# I2C_Line_Sensor.net
KiCad netlist of a schematic drawn in EAGLE
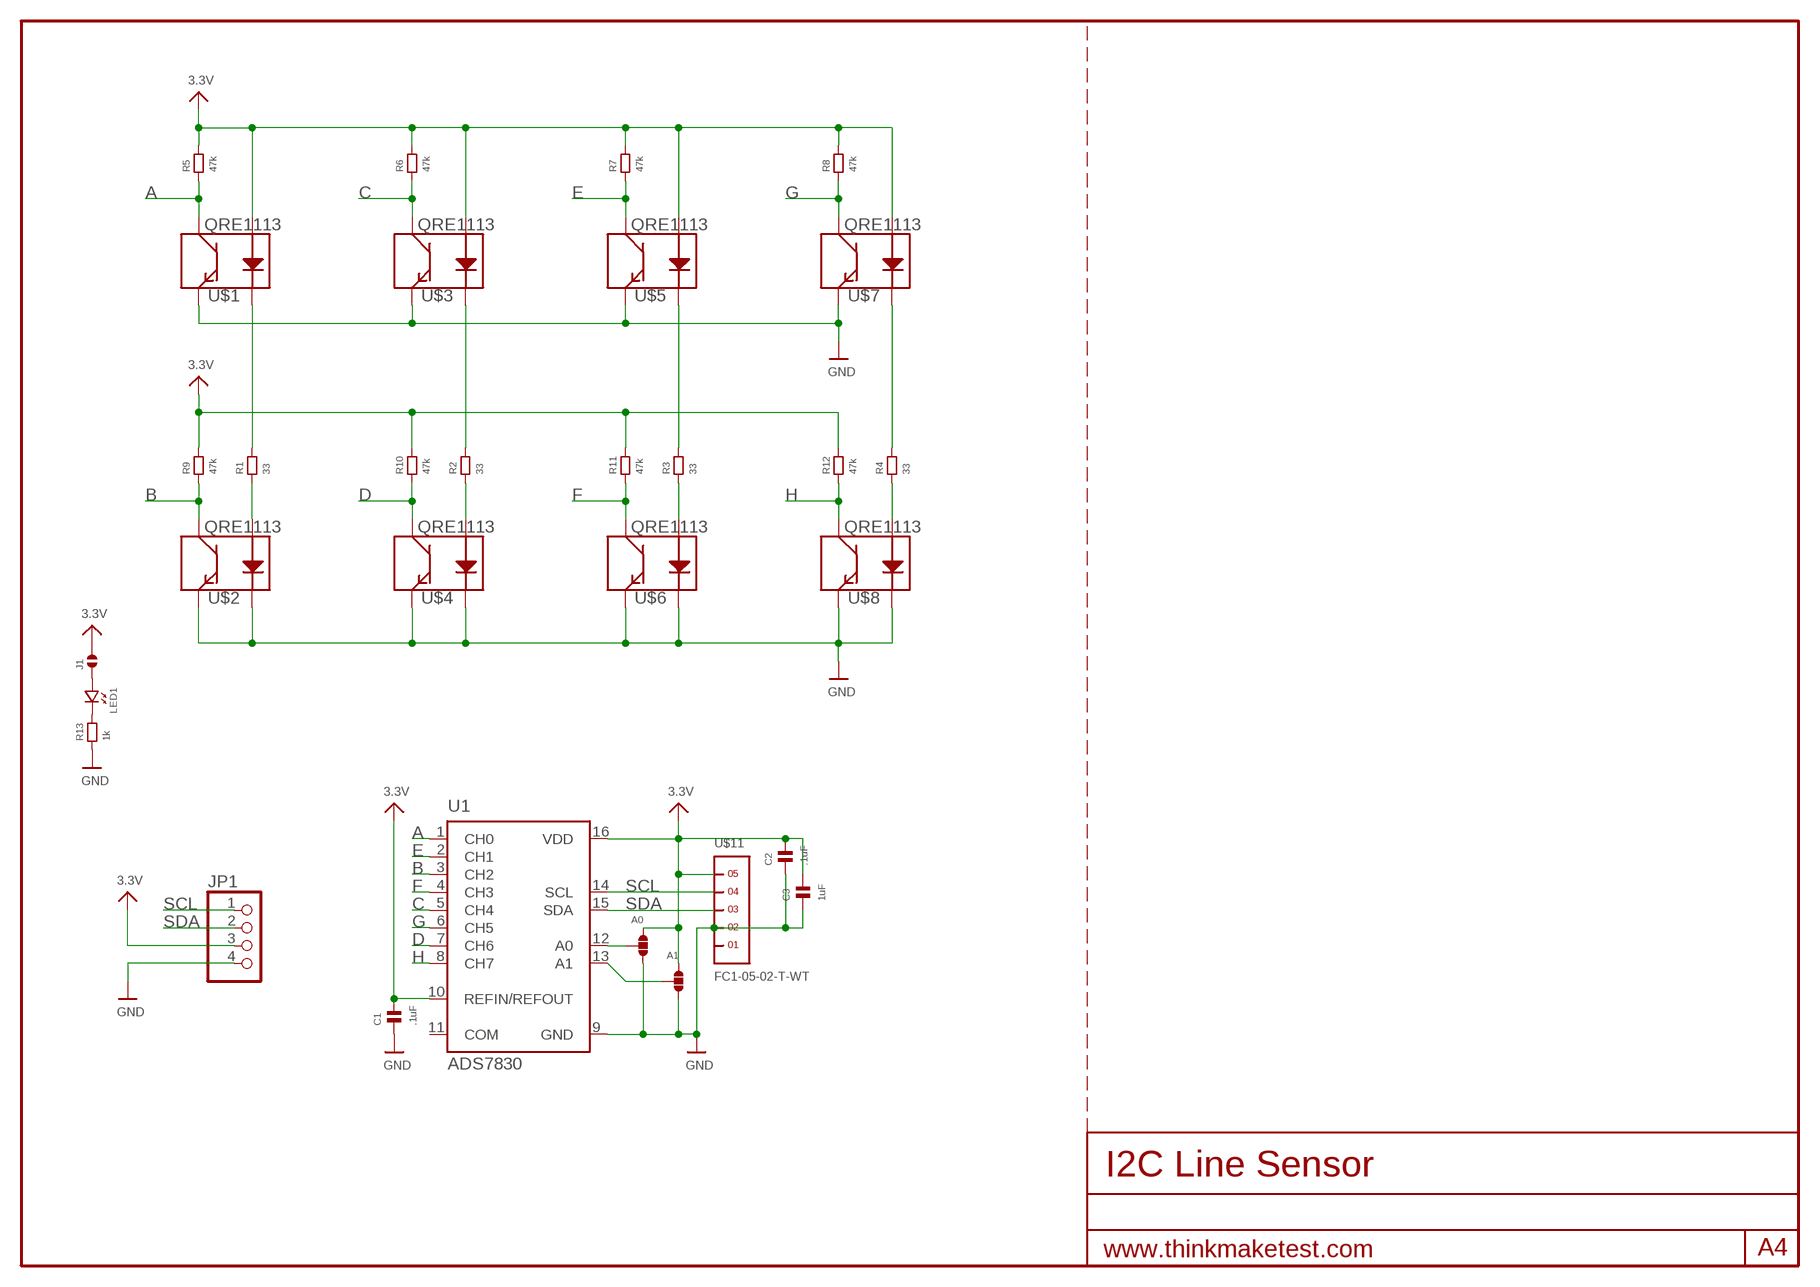
[diagram p0: schematic, sheet 1]

(export (version "E")
  (design (tool "Eeschema 10.0.6"))
  (components
    (comp (ref "A0")
      (value "SOLDERJUMPER.3.LRG.23")
      (footprint "eagle-import:3.LRG.23")
      (libsource (lib "eagle-import") (part "SOLDERJUMPER.3.LRG.23"))
    )
    (comp (ref "A1")
      (value "SOLDERJUMPER.3.LRG.23")
      (footprint "eagle-import:3.LRG.23")
      (libsource (lib "eagle-import") (part "SOLDERJUMPER.3.LRG.23"))
    )
    (comp (ref "C1")
      (value ".1uF")
      (footprint "eagle-import:0603")
      (libsource (lib "eagle-import") (part "CAPACITOR.0603"))
    )
    (comp (ref "C2")
      (value ".1uF")
      (footprint "eagle-import:0603")
      (libsource (lib "eagle-import") (part "CAPACITOR.0603"))
    )
    (comp (ref "C3")
      (value "1uF")
      (footprint "eagle-import:0603")
      (libsource (lib "eagle-import") (part "CAPACITOR.0603"))
    )
    (comp (ref "J1")
      (value "SOLDERJUMPER.2.MED")
      (footprint "eagle-import:2.MED")
      (libsource (lib "eagle-import") (part "SOLDERJUMPER.2.MED"))
    )
    (comp (ref "JP1")
      (value "HEADER-1X4")
      (footprint "eagle-import:1X04_OVAL")
      (libsource (lib "eagle-import") (part "HEADER-1X4"))
    )
    (comp (ref "LED1")
      (value "LED.0603")
      (footprint "eagle-import:0603.LED")
      (libsource (lib "eagle-import") (part "LED.0603"))
    )
    (comp (ref "R1")
      (value "33")
      (footprint "eagle-import:0603")
      (libsource (lib "eagle-import") (part "RESISTOR.0603"))
    )
    (comp (ref "R2")
      (value "33")
      (footprint "eagle-import:0603")
      (libsource (lib "eagle-import") (part "RESISTOR.0603"))
    )
    (comp (ref "R3")
      (value "33")
      (footprint "eagle-import:0603")
      (libsource (lib "eagle-import") (part "RESISTOR.0603"))
    )
    (comp (ref "R4")
      (value "33")
      (footprint "eagle-import:0603")
      (libsource (lib "eagle-import") (part "RESISTOR.0603"))
    )
    (comp (ref "R5")
      (value "47k")
      (footprint "eagle-import:0603")
      (libsource (lib "eagle-import") (part "RESISTOR.0603"))
    )
    (comp (ref "R6")
      (value "47k")
      (footprint "eagle-import:0603")
      (libsource (lib "eagle-import") (part "RESISTOR.0603"))
    )
    (comp (ref "R7")
      (value "47k")
      (footprint "eagle-import:0603")
      (libsource (lib "eagle-import") (part "RESISTOR.0603"))
    )
    (comp (ref "R8")
      (value "47k")
      (footprint "eagle-import:0603")
      (libsource (lib "eagle-import") (part "RESISTOR.0603"))
    )
    (comp (ref "R9")
      (value "47k")
      (footprint "eagle-import:0603")
      (libsource (lib "eagle-import") (part "RESISTOR.0603"))
    )
    (comp (ref "R10")
      (value "47k")
      (footprint "eagle-import:0603")
      (libsource (lib "eagle-import") (part "RESISTOR.0603"))
    )
    (comp (ref "R11")
      (value "47k")
      (footprint "eagle-import:0603")
      (libsource (lib "eagle-import") (part "RESISTOR.0603"))
    )
    (comp (ref "R12")
      (value "47k")
      (footprint "eagle-import:0603")
      (libsource (lib "eagle-import") (part "RESISTOR.0603"))
    )
    (comp (ref "R13")
      (value "1k")
      (footprint "eagle-import:0603")
      (libsource (lib "eagle-import") (part "RESISTOR.0603"))
    )
    (comp (ref "U$1")
      (value "QRE1113")
      (footprint "eagle-import:QRE1113")
      (libsource (lib "eagle-import") (part "QRE1113"))
    )
    (comp (ref "U$2")
      (value "QRE1113")
      (footprint "eagle-import:QRE1113")
      (libsource (lib "eagle-import") (part "QRE1113"))
    )
    (comp (ref "U$3")
      (value "QRE1113")
      (footprint "eagle-import:QRE1113")
      (libsource (lib "eagle-import") (part "QRE1113"))
    )
    (comp (ref "U$4")
      (value "QRE1113")
      (footprint "eagle-import:QRE1113")
      (libsource (lib "eagle-import") (part "QRE1113"))
    )
    (comp (ref "U$5")
      (value "QRE1113")
      (footprint "eagle-import:QRE1113")
      (libsource (lib "eagle-import") (part "QRE1113"))
    )
    (comp (ref "U$6")
      (value "QRE1113")
      (footprint "eagle-import:QRE1113")
      (libsource (lib "eagle-import") (part "QRE1113"))
    )
    (comp (ref "U$7")
      (value "QRE1113")
      (footprint "eagle-import:QRE1113")
      (libsource (lib "eagle-import") (part "QRE1113"))
    )
    (comp (ref "U$8")
      (value "QRE1113")
      (footprint "eagle-import:QRE1113")
      (libsource (lib "eagle-import") (part "QRE1113"))
    )
    (comp (ref "U$11")
      (value "FC1-05-02-T-WT")
      (footprint "eagle-import:FC1-05-02-T-WT")
      (libsource (lib "eagle-import") (part "FC1-05-02-T-WT"))
    )
    (comp (ref "U1")
      (value "ADS7830")
      (footprint "eagle-import:TSSOP16-PW")
      (libsource (lib "eagle-import") (part "ADS7828"))
    )
  )
  (nets
    (net (code "1") (name "/A") (class "Default")
      (node (ref "R5") (pin "1") (pinfunction "1_1") (pintype "bidirectional"))
      (node (ref "U$1") (pin "3") (pinfunction "C_3") (pintype "bidirectional"))
      (node (ref "U1") (pin "1") (pinfunction "CH0_1") (pintype "input"))
    )
    (net (code "2") (name "/B") (class "Default")
      (node (ref "R9") (pin "1") (pinfunction "1_1") (pintype "bidirectional"))
      (node (ref "U$2") (pin "3") (pinfunction "C_3") (pintype "bidirectional"))
      (node (ref "U1") (pin "3") (pinfunction "CH2_3") (pintype "input"))
    )
    (net (code "3") (name "/C") (class "Default")
      (node (ref "R6") (pin "1") (pinfunction "1_1") (pintype "bidirectional"))
      (node (ref "U$3") (pin "3") (pinfunction "C_3") (pintype "bidirectional"))
      (node (ref "U1") (pin "5") (pinfunction "CH4_5") (pintype "input"))
    )
    (net (code "4") (name "/D") (class "Default")
      (node (ref "R10") (pin "1") (pinfunction "1_1") (pintype "bidirectional"))
      (node (ref "U$4") (pin "3") (pinfunction "C_3") (pintype "bidirectional"))
      (node (ref "U1") (pin "7") (pinfunction "CH6_7") (pintype "input"))
    )
    (net (code "5") (name "/E") (class "Default")
      (node (ref "R7") (pin "1") (pinfunction "1_1") (pintype "bidirectional"))
      (node (ref "U$5") (pin "3") (pinfunction "C_3") (pintype "bidirectional"))
      (node (ref "U1") (pin "2") (pinfunction "CH1_2") (pintype "input"))
    )
    (net (code "6") (name "/F") (class "Default")
      (node (ref "R11") (pin "1") (pinfunction "1_1") (pintype "bidirectional"))
      (node (ref "U$6") (pin "3") (pinfunction "C_3") (pintype "bidirectional"))
      (node (ref "U1") (pin "4") (pinfunction "CH3_4") (pintype "input"))
    )
    (net (code "7") (name "/G") (class "Default")
      (node (ref "R8") (pin "1") (pinfunction "1_1") (pintype "bidirectional"))
      (node (ref "U$7") (pin "3") (pinfunction "C_3") (pintype "bidirectional"))
      (node (ref "U1") (pin "6") (pinfunction "CH5_6") (pintype "input"))
    )
    (net (code "8") (name "/H") (class "Default")
      (node (ref "R12") (pin "1") (pinfunction "1_1") (pintype "bidirectional"))
      (node (ref "U$8") (pin "3") (pinfunction "C_3") (pintype "bidirectional"))
      (node (ref "U1") (pin "8") (pinfunction "CH7_8") (pintype "input"))
    )
    (net (code "9") (name "/SCL") (class "Default")
      (node (ref "JP1") (pin "1") (pinfunction "1_1") (pintype "passive"))
      (node (ref "U$11") (pin "4") (pinfunction "4_4") (pintype "bidirectional"))
      (node (ref "U1") (pin "14") (pinfunction "SCL_14") (pintype "input"))
    )
    (net (code "10") (name "/SDA") (class "Default")
      (node (ref "JP1") (pin "2") (pinfunction "2_2") (pintype "passive"))
      (node (ref "U$11") (pin "3") (pinfunction "3_3") (pintype "bidirectional"))
      (node (ref "U1") (pin "15") (pinfunction "SDA_15") (pintype "bidirectional"))
    )
    (net (code "11") (name "3.3V") (class "Default")
      (node (ref "A0") (pin "1") (pinfunction "1_1") (pintype "bidirectional"))
      (node (ref "A1") (pin "1") (pinfunction "1_1") (pintype "bidirectional"))
      (node (ref "C1") (pin "2") (pinfunction "2_2") (pintype "bidirectional"))
      (node (ref "C2") (pin "2") (pinfunction "2_2") (pintype "bidirectional"))
      (node (ref "C3") (pin "2") (pinfunction "2_2") (pintype "bidirectional"))
      (node (ref "J1") (pin "2") (pinfunction "2_2") (pintype "bidirectional"))
      (node (ref "JP1") (pin "3") (pinfunction "3_3") (pintype "passive"))
      (node (ref "R10") (pin "2") (pinfunction "2_2") (pintype "bidirectional"))
      (node (ref "R11") (pin "2") (pinfunction "2_2") (pintype "bidirectional"))
      (node (ref "R12") (pin "2") (pinfunction "2_2") (pintype "bidirectional"))
      (node (ref "R5") (pin "2") (pinfunction "2_2") (pintype "bidirectional"))
      (node (ref "R6") (pin "2") (pinfunction "2_2") (pintype "bidirectional"))
      (node (ref "R7") (pin "2") (pinfunction "2_2") (pintype "bidirectional"))
      (node (ref "R8") (pin "2") (pinfunction "2_2") (pintype "bidirectional"))
      (node (ref "R9") (pin "2") (pinfunction "2_2") (pintype "bidirectional"))
      (node (ref "U$1") (pin "1") (pinfunction "A_1") (pintype "bidirectional"))
      (node (ref "U$11") (pin "5") (pinfunction "5_5") (pintype "bidirectional"))
      (node (ref "U$3") (pin "1") (pinfunction "A_1") (pintype "bidirectional"))
      (node (ref "U$5") (pin "1") (pinfunction "A_1") (pintype "bidirectional"))
      (node (ref "U$7") (pin "1") (pinfunction "A_1") (pintype "bidirectional"))
      (node (ref "U1") (pin "10") (pinfunction "REFIN/REFOUT_10") (pintype "passive"))
      (node (ref "U1") (pin "16") (pinfunction "VDD_16") (pintype "power_in"))
    )
    (net (code "12") (name "GND") (class "Default")
      (node (ref "A0") (pin "3") (pinfunction "3_3") (pintype "bidirectional"))
      (node (ref "A1") (pin "3") (pinfunction "3_3") (pintype "bidirectional"))
      (node (ref "C1") (pin "1") (pinfunction "1_1") (pintype "bidirectional"))
      (node (ref "C2") (pin "1") (pinfunction "1_1") (pintype "bidirectional"))
      (node (ref "C3") (pin "1") (pinfunction "1_1") (pintype "bidirectional"))
      (node (ref "JP1") (pin "4") (pinfunction "4_4") (pintype "passive"))
      (node (ref "R13") (pin "1") (pinfunction "1_1") (pintype "bidirectional"))
      (node (ref "U$1") (pin "4") (pinfunction "E_4") (pintype "bidirectional"))
      (node (ref "U$11") (pin "2") (pinfunction "2_2") (pintype "bidirectional"))
      (node (ref "U$2") (pin "2") (pinfunction "K_2") (pintype "bidirectional"))
      (node (ref "U$2") (pin "4") (pinfunction "E_4") (pintype "bidirectional"))
      (node (ref "U$3") (pin "4") (pinfunction "E_4") (pintype "bidirectional"))
      (node (ref "U$4") (pin "2") (pinfunction "K_2") (pintype "bidirectional"))
      (node (ref "U$4") (pin "4") (pinfunction "E_4") (pintype "bidirectional"))
      (node (ref "U$5") (pin "4") (pinfunction "E_4") (pintype "bidirectional"))
      (node (ref "U$6") (pin "2") (pinfunction "K_2") (pintype "bidirectional"))
      (node (ref "U$6") (pin "4") (pinfunction "E_4") (pintype "bidirectional"))
      (node (ref "U$7") (pin "4") (pinfunction "E_4") (pintype "bidirectional"))
      (node (ref "U$8") (pin "2") (pinfunction "K_2") (pintype "bidirectional"))
      (node (ref "U$8") (pin "4") (pinfunction "E_4") (pintype "bidirectional"))
      (node (ref "U1") (pin "9") (pinfunction "GND_9") (pintype "power_in"))
    )
    (net (code "13") (name "Net-(LED1-1)") (class "Default")
      (node (ref "J1") (pin "1") (pinfunction "1_1") (pintype "bidirectional"))
      (node (ref "LED1") (pin "P$1") (pinfunction "1_P$1") (pintype "bidirectional"))
    )
    (net (code "14") (name "Net-(LED1-2)") (class "Default")
      (node (ref "LED1") (pin "P$2") (pinfunction "2_P$2") (pintype "bidirectional"))
      (node (ref "R13") (pin "2") (pinfunction "2_2") (pintype "bidirectional"))
    )
    (net (code "15") (name "Net-(U$1-K)") (class "Default")
      (node (ref "R1") (pin "2") (pinfunction "2_2") (pintype "bidirectional"))
      (node (ref "U$1") (pin "2") (pinfunction "K_2") (pintype "bidirectional"))
    )
    (net (code "16") (name "Net-(U$2-A)") (class "Default")
      (node (ref "R1") (pin "1") (pinfunction "1_1") (pintype "bidirectional"))
      (node (ref "U$2") (pin "1") (pinfunction "A_1") (pintype "bidirectional"))
    )
    (net (code "17") (name "Net-(U$3-K)") (class "Default")
      (node (ref "R2") (pin "2") (pinfunction "2_2") (pintype "bidirectional"))
      (node (ref "U$3") (pin "2") (pinfunction "K_2") (pintype "bidirectional"))
    )
    (net (code "18") (name "Net-(U$4-A)") (class "Default")
      (node (ref "R2") (pin "1") (pinfunction "1_1") (pintype "bidirectional"))
      (node (ref "U$4") (pin "1") (pinfunction "A_1") (pintype "bidirectional"))
    )
    (net (code "19") (name "Net-(U$5-K)") (class "Default")
      (node (ref "R3") (pin "2") (pinfunction "2_2") (pintype "bidirectional"))
      (node (ref "U$5") (pin "2") (pinfunction "K_2") (pintype "bidirectional"))
    )
    (net (code "20") (name "Net-(U$6-A)") (class "Default")
      (node (ref "R3") (pin "1") (pinfunction "1_1") (pintype "bidirectional"))
      (node (ref "U$6") (pin "1") (pinfunction "A_1") (pintype "bidirectional"))
    )
    (net (code "21") (name "Net-(U$7-K)") (class "Default")
      (node (ref "R4") (pin "2") (pinfunction "2_2") (pintype "bidirectional"))
      (node (ref "U$7") (pin "2") (pinfunction "K_2") (pintype "bidirectional"))
    )
    (net (code "22") (name "Net-(U$8-A)") (class "Default")
      (node (ref "R4") (pin "1") (pinfunction "1_1") (pintype "bidirectional"))
      (node (ref "U$8") (pin "1") (pinfunction "A_1") (pintype "bidirectional"))
    )
    (net (code "23") (name "Net-(U1-A0)") (class "Default")
      (node (ref "A0") (pin "2") (pinfunction "2_2") (pintype "bidirectional"))
      (node (ref "U1") (pin "12") (pinfunction "A0_12") (pintype "input"))
    )
    (net (code "24") (name "Net-(U1-A1)") (class "Default")
      (node (ref "A1") (pin "2") (pinfunction "2_2") (pintype "bidirectional"))
      (node (ref "U1") (pin "13") (pinfunction "A1_13") (pintype "input"))
    )
    (net (code "25") (name "unconnected-(U$11-Pad1)") (class "Default")
      (node (ref "U$11") (pin "1") (pinfunction "1_1") (pintype "bidirectional"))
    )
    (net (code "26") (name "unconnected-(U1-COM-Pad11)") (class "Default")
      (node (ref "U1") (pin "11") (pinfunction "COM_11") (pintype "input"))
    )
  )
)
